# relay.net
KiCad netlist of a schematic drawn in EAGLE
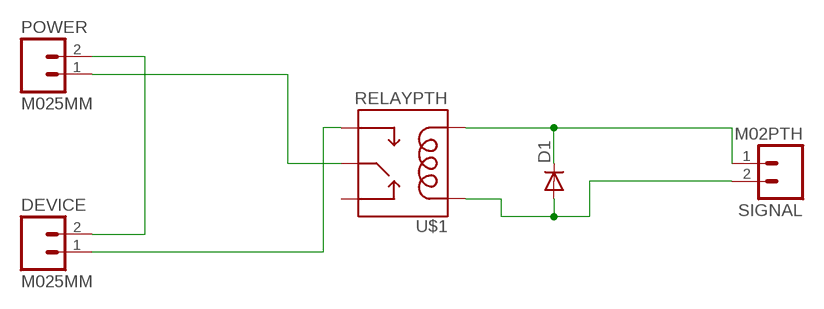
[diagram p0: schematic, sheet 1]

(export (version "E")
  (design (tool "Eeschema 10.0.6"))
  (components
    (comp (ref "D1")
      (value "DIODE1N4148")
      (footprint "eagle-import:DIODE-1N4148")
      (libsource (lib "eagle-import") (part "DIODE1N4148"))
    )
    (comp (ref "DEVICE")
      (value "M025MM")
      (footprint "eagle-import:SCREWTERMINAL-5MM-2")
      (libsource (lib "eagle-import") (part "M025MM"))
    )
    (comp (ref "POWER")
      (value "M025MM")
      (footprint "eagle-import:SCREWTERMINAL-5MM-2")
      (libsource (lib "eagle-import") (part "M025MM"))
    )
    (comp (ref "SIGNAL")
      (value "M02PTH")
      (footprint "eagle-import:1X02")
      (libsource (lib "eagle-import") (part "M02PTH"))
    )
    (comp (ref "U$1")
      (value "RELAYPTH")
      (footprint "eagle-import:RELAY-G5Q")
      (libsource (lib "eagle-import") (part "RELAYPTH"))
    )
  )
  (nets
    (net (code "1") (name "Net-(DEVICE-Pad2)") (class "Default")
      (node (ref "DEVICE") (pin "2") (pinfunction "2_2") (pintype "passive"))
      (node (ref "POWER") (pin "2") (pinfunction "2_2") (pintype "passive"))
    )
    (net (code "2") (name "Net-(U$1-COIL1)") (class "Default")
      (node (ref "D1") (pin "A") (pinfunction "A_A") (pintype "passive"))
      (node (ref "SIGNAL") (pin "2") (pinfunction "2_2") (pintype "passive"))
      (node (ref "U$1") (pin "5") (pinfunction "COIL1_5") (pintype "bidirectional"))
    )
    (net (code "3") (name "Net-(U$1-COIL2)") (class "Default")
      (node (ref "D1") (pin "C") (pinfunction "C_C") (pintype "passive"))
      (node (ref "SIGNAL") (pin "1") (pinfunction "1_1") (pintype "passive"))
      (node (ref "U$1") (pin "1") (pinfunction "COIL2_1") (pintype "bidirectional"))
    )
    (net (code "4") (name "Net-(U$1-MAIN)") (class "Default")
      (node (ref "POWER") (pin "1") (pinfunction "1_1") (pintype "passive"))
      (node (ref "U$1") (pin "2") (pinfunction "MAIN_2") (pintype "bidirectional"))
    )
    (net (code "5") (name "Net-(U$1-NO)") (class "Default")
      (node (ref "DEVICE") (pin "1") (pinfunction "1_1") (pintype "passive"))
      (node (ref "U$1") (pin "3") (pinfunction "NO_3") (pintype "bidirectional"))
    )
    (net (code "6") (name "unconnected-(U$1-NC-Pad4)") (class "Default")
      (node (ref "U$1") (pin "4") (pinfunction "NC_4") (pintype "bidirectional"))
    )
  )
)
